# BusinessCard.net
KiCad netlist of a schematic drawn in EAGLE
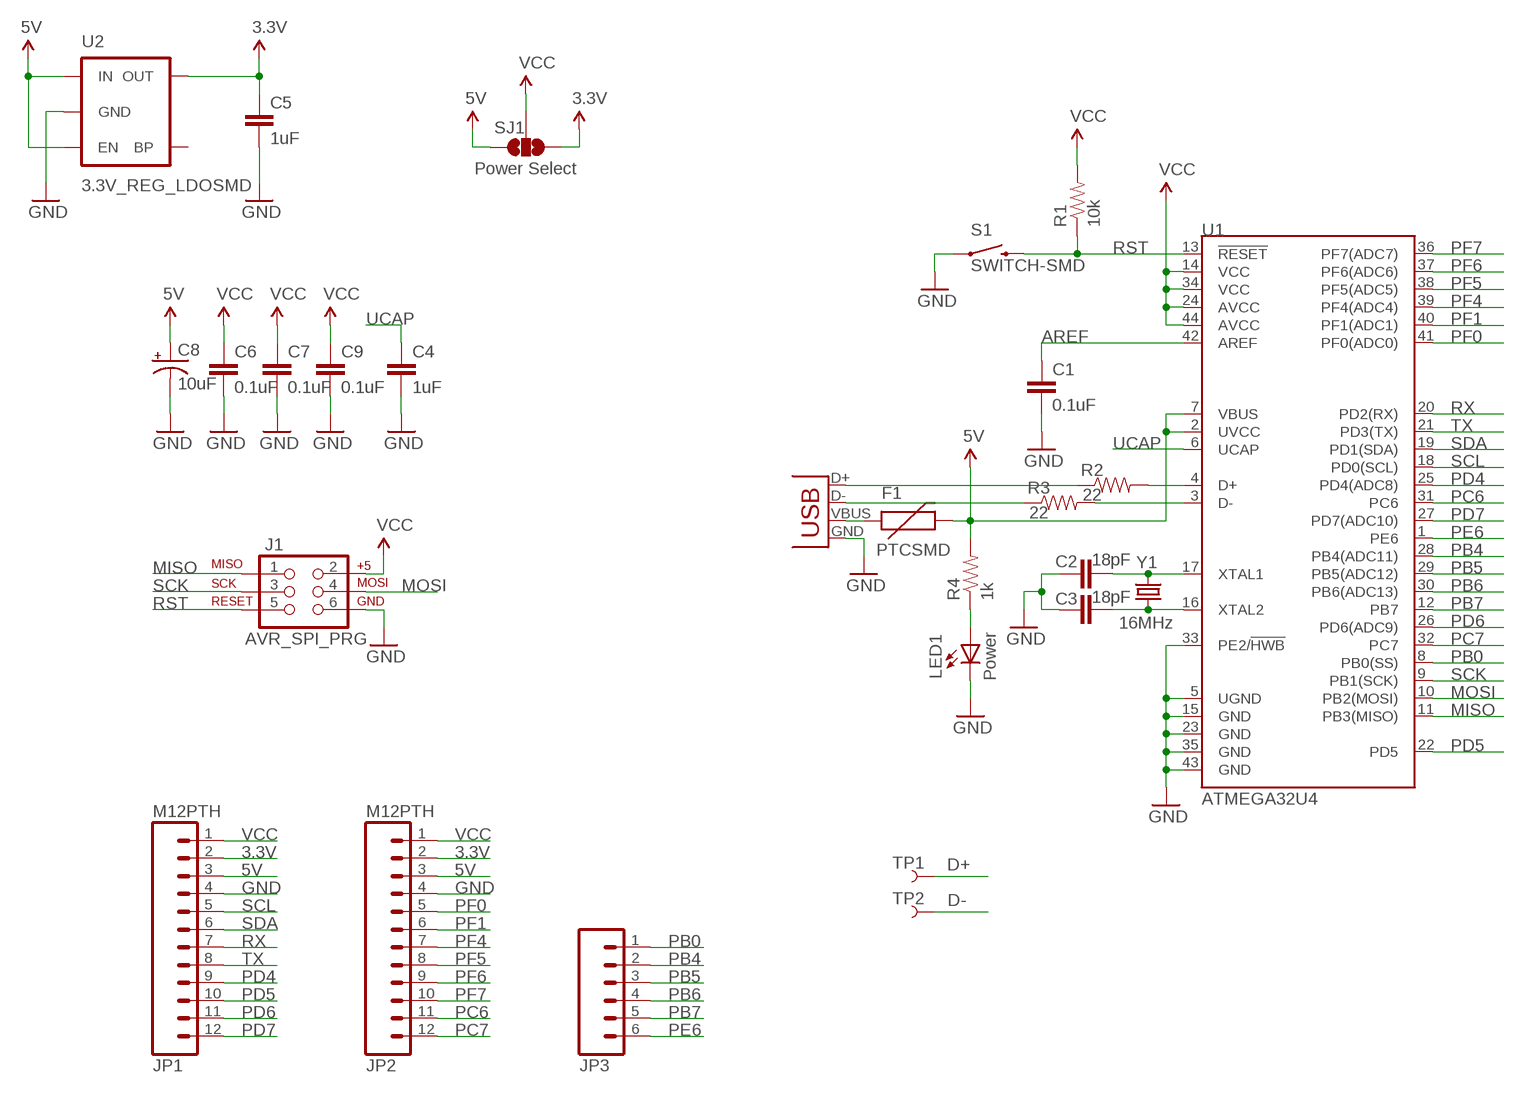
[diagram p0: schematic, sheet 1]

(export (version "E")
  (design (tool "Eeschema 10.0.6"))
  (components
    (comp (ref "C1")
      (value "0.1uF")
      (footprint "eagle-import:0402-CAP")
      (libsource (lib "eagle-import") (part "CAP0402-CAP"))
    )
    (comp (ref "C2")
      (value "18pF")
      (footprint "eagle-import:0402-CAP")
      (libsource (lib "eagle-import") (part "CAP0402-CAP"))
    )
    (comp (ref "C3")
      (value "18pF")
      (footprint "eagle-import:0402-CAP")
      (libsource (lib "eagle-import") (part "CAP0402-CAP"))
    )
    (comp (ref "C4")
      (value "1uF")
      (footprint "eagle-import:0402-CAP")
      (libsource (lib "eagle-import") (part "CAP0402-CAP"))
    )
    (comp (ref "C5")
      (value "1uF")
      (footprint "eagle-import:0402-CAP")
      (libsource (lib "eagle-import") (part "CAP0402-CAP"))
    )
    (comp (ref "C6")
      (value "0.1uF")
      (footprint "eagle-import:0402-CAP")
      (libsource (lib "eagle-import") (part "CAP0402-CAP"))
    )
    (comp (ref "C7")
      (value "0.1uF")
      (footprint "eagle-import:0402-CAP")
      (libsource (lib "eagle-import") (part "CAP0402-CAP"))
    )
    (comp (ref "C8")
      (value "10uF")
      (footprint "eagle-import:EIA3216")
      (libsource (lib "eagle-import") (part "CAP_POL1206"))
    )
    (comp (ref "C9")
      (value "0.1uF")
      (footprint "eagle-import:0402-CAP")
      (libsource (lib "eagle-import") (part "CAP0402-CAP"))
    )
    (comp (ref "F1")
      (value "PTCSMD")
      (footprint "eagle-import:PTC-1206")
      (libsource (lib "eagle-import") (part "PTCSMD"))
    )
    (comp (ref "J1")
      (value "AVR_SPI_PRG")
      (footprint "eagle-import:2X3")
      (libsource (lib "eagle-import") (part "AVR_SPI_PRG_6PTH"))
    )
    (comp (ref "JP1")
      (value "M12PTH")
      (footprint "eagle-import:1X12")
      (libsource (lib "eagle-import") (part "M12PTH"))
    )
    (comp (ref "JP2")
      (value "M12PTH")
      (footprint "eagle-import:1X12")
      (libsource (lib "eagle-import") (part "M12PTH"))
    )
    (comp (ref "JP3")
      (value "M06SIP")
      (footprint "eagle-import:1X06")
      (libsource (lib "eagle-import") (part "M06SIP"))
    )
    (comp (ref "LED1")
      (value "Power")
      (footprint "eagle-import:LED-0603")
      (libsource (lib "eagle-import") (part "LED0603"))
    )
    (comp (ref "R1")
      (value "10k")
      (footprint "eagle-import:0402-RES")
      (libsource (lib "eagle-import") (part "RESISTOR0402-RES"))
    )
    (comp (ref "R2")
      (value "22")
      (footprint "eagle-import:0402-RES")
      (libsource (lib "eagle-import") (part "RESISTOR0402-RES"))
    )
    (comp (ref "R3")
      (value "22")
      (footprint "eagle-import:0402-RES")
      (libsource (lib "eagle-import") (part "RESISTOR0402-RES"))
    )
    (comp (ref "R4")
      (value "1k")
      (footprint "eagle-import:0402-RES")
      (libsource (lib "eagle-import") (part "RESISTOR0402-RES"))
    )
    (comp (ref "S1")
      (value "SWITCH-SMD")
      (footprint "eagle-import:TACTILE_SWITCH_SMD")
      (libsource (lib "eagle-import") (part "SWITCH-MOMENTARY-2SMD"))
    )
    (comp (ref "SJ1")
      (value "Power Select")
      (footprint "eagle-import:SJ_3_PASTE2&3")
      (libsource (lib "eagle-import") (part "SOLDERJUMPER_2WAYPASTE2&3"))
    )
    (comp (ref "TP1")
      (value "TEST-POINT3")
      (footprint "eagle-import:PAD.03X.03")
      (libsource (lib "eagle-import") (part "TEST-POINT3"))
    )
    (comp (ref "TP2")
      (value "TEST-POINT3")
      (footprint "eagle-import:PAD.03X.03")
      (libsource (lib "eagle-import") (part "TEST-POINT3"))
    )
    (comp (ref "U1")
      (value "ATMEGA32U4")
      (footprint "eagle-import:QFN-44-NOPAD")
      (libsource (lib "eagle-import") (part "ATMEGA32U4QFN2"))
    )
    (comp (ref "U2")
      (value "3.3V_REG_LDOSMD")
      (footprint "eagle-import:SOT23-5")
      (libsource (lib "eagle-import") (part "V_REG_LDOSMD"))
    )
    (comp (ref "X1")
      (value "USBSMD")
      (footprint "eagle-import:USB-MINIB")
      (libsource (lib "eagle-import") (part "USBSMD"))
    )
    (comp (ref "Y1")
      (value "16MHz")
      (footprint "eagle-import:CRYSTAL-SMD-5X3")
      (libsource (lib "eagle-import") (part "CRYSTAL5X3"))
    )
  )
  (nets
    (net (code "1") (name "/AREF") (class "Default")
      (node (ref "C1") (pin "1") (pinfunction "1_1") (pintype "passive"))
      (node (ref "U1") (pin "42") (pinfunction "AREF_42") (pintype "bidirectional"))
    )
    (net (code "2") (name "/D+") (class "Default")
      (node (ref "R2") (pin "1") (pinfunction "1_1") (pintype "passive"))
      (node (ref "TP1") (pin "P$1") (pinfunction "1_P$1") (pintype "bidirectional"))
      (node (ref "X1") (pin "D+") (pinfunction "D+_D+") (pintype "bidirectional"))
    )
    (net (code "3") (name "/D-") (class "Default")
      (node (ref "R3") (pin "1") (pinfunction "1_1") (pintype "passive"))
      (node (ref "TP2") (pin "P$1") (pinfunction "1_P$1") (pintype "bidirectional"))
      (node (ref "X1") (pin "D-") (pinfunction "D-_D-") (pintype "bidirectional"))
    )
    (net (code "4") (name "/MISO") (class "Default")
      (node (ref "J1") (pin "1") (pinfunction "1_1") (pintype "passive"))
      (node (ref "U1") (pin "11") (pinfunction "PB3(MISO)_11") (pintype "bidirectional"))
    )
    (net (code "5") (name "/MOSI") (class "Default")
      (node (ref "J1") (pin "4") (pinfunction "4_4") (pintype "passive"))
      (node (ref "U1") (pin "10") (pinfunction "PB2(MOSI)_10") (pintype "bidirectional"))
    )
    (net (code "6") (name "/PB0") (class "Default")
      (node (ref "JP3") (pin "1") (pinfunction "1_1") (pintype "passive"))
      (node (ref "U1") (pin "8") (pinfunction "PB0(SS)_8") (pintype "bidirectional"))
    )
    (net (code "7") (name "/PB4") (class "Default")
      (node (ref "JP3") (pin "2") (pinfunction "2_2") (pintype "passive"))
      (node (ref "U1") (pin "28") (pinfunction "PB4(ADC11)_28") (pintype "bidirectional"))
    )
    (net (code "8") (name "/PB5") (class "Default")
      (node (ref "JP3") (pin "3") (pinfunction "3_3") (pintype "passive"))
      (node (ref "U1") (pin "29") (pinfunction "PB5(ADC12)_29") (pintype "bidirectional"))
    )
    (net (code "9") (name "/PB6") (class "Default")
      (node (ref "JP3") (pin "4") (pinfunction "4_4") (pintype "passive"))
      (node (ref "U1") (pin "30") (pinfunction "PB6(ADC13)_30") (pintype "bidirectional"))
    )
    (net (code "10") (name "/PB7") (class "Default")
      (node (ref "JP3") (pin "5") (pinfunction "5_5") (pintype "passive"))
      (node (ref "U1") (pin "12") (pinfunction "PB7_12") (pintype "bidirectional"))
    )
    (net (code "11") (name "/PC6") (class "Default")
      (node (ref "JP2") (pin "11") (pinfunction "11_11") (pintype "passive"))
      (node (ref "U1") (pin "31") (pinfunction "PC6_31") (pintype "bidirectional"))
    )
    (net (code "12") (name "/PC7") (class "Default")
      (node (ref "JP2") (pin "12") (pinfunction "12_12") (pintype "passive"))
      (node (ref "U1") (pin "32") (pinfunction "PC7_32") (pintype "bidirectional"))
    )
    (net (code "13") (name "/PD4") (class "Default")
      (node (ref "JP1") (pin "9") (pinfunction "9_9") (pintype "passive"))
      (node (ref "U1") (pin "25") (pinfunction "PD4(ADC8)_25") (pintype "bidirectional"))
    )
    (net (code "14") (name "/PD5") (class "Default")
      (node (ref "JP1") (pin "10") (pinfunction "10_10") (pintype "passive"))
      (node (ref "U1") (pin "22") (pinfunction "PD5_22") (pintype "bidirectional"))
    )
    (net (code "15") (name "/PD6") (class "Default")
      (node (ref "JP1") (pin "11") (pinfunction "11_11") (pintype "passive"))
      (node (ref "U1") (pin "26") (pinfunction "PD6(ADC9)_26") (pintype "bidirectional"))
    )
    (net (code "16") (name "/PD7") (class "Default")
      (node (ref "JP1") (pin "12") (pinfunction "12_12") (pintype "passive"))
      (node (ref "U1") (pin "27") (pinfunction "PD7(ADC10)_27") (pintype "bidirectional"))
    )
    (net (code "17") (name "/PE6") (class "Default")
      (node (ref "JP3") (pin "6") (pinfunction "6_6") (pintype "passive"))
      (node (ref "U1") (pin "1") (pinfunction "PE6_1") (pintype "bidirectional"))
    )
    (net (code "18") (name "/PF0") (class "Default")
      (node (ref "JP2") (pin "5") (pinfunction "5_5") (pintype "passive"))
      (node (ref "U1") (pin "41") (pinfunction "PF0(ADC0)_41") (pintype "bidirectional"))
    )
    (net (code "19") (name "/PF1") (class "Default")
      (node (ref "JP2") (pin "6") (pinfunction "6_6") (pintype "passive"))
      (node (ref "U1") (pin "40") (pinfunction "PF1(ADC1)_40") (pintype "bidirectional"))
    )
    (net (code "20") (name "/PF4") (class "Default")
      (node (ref "JP2") (pin "7") (pinfunction "7_7") (pintype "passive"))
      (node (ref "U1") (pin "39") (pinfunction "PF4(ADC4)_39") (pintype "bidirectional"))
    )
    (net (code "21") (name "/PF5") (class "Default")
      (node (ref "JP2") (pin "8") (pinfunction "8_8") (pintype "passive"))
      (node (ref "U1") (pin "38") (pinfunction "PF5(ADC5)_38") (pintype "bidirectional"))
    )
    (net (code "22") (name "/PF6") (class "Default")
      (node (ref "JP2") (pin "9") (pinfunction "9_9") (pintype "passive"))
      (node (ref "U1") (pin "37") (pinfunction "PF6(ADC6)_37") (pintype "bidirectional"))
    )
    (net (code "23") (name "/PF7") (class "Default")
      (node (ref "JP2") (pin "10") (pinfunction "10_10") (pintype "passive"))
      (node (ref "U1") (pin "36") (pinfunction "PF7(ADC7)_36") (pintype "bidirectional"))
    )
    (net (code "24") (name "/RST") (class "Default")
      (node (ref "J1") (pin "5") (pinfunction "5_5") (pintype "passive"))
      (node (ref "R1") (pin "1") (pinfunction "1_1") (pintype "passive"))
      (node (ref "S1") (pin "3") (pinfunction "2_3") (pintype "passive"))
      (node (ref "U1") (pin "13") (pinfunction "~{RESET}_13") (pintype "bidirectional"))
    )
    (net (code "25") (name "/RX") (class "Default")
      (node (ref "JP1") (pin "7") (pinfunction "7_7") (pintype "passive"))
      (node (ref "U1") (pin "20") (pinfunction "PD2(RX)_20") (pintype "bidirectional"))
    )
    (net (code "26") (name "/SCK") (class "Default")
      (node (ref "J1") (pin "3") (pinfunction "3_3") (pintype "passive"))
      (node (ref "U1") (pin "9") (pinfunction "PB1(SCK)_9") (pintype "bidirectional"))
    )
    (net (code "27") (name "/SCL") (class "Default")
      (node (ref "JP1") (pin "5") (pinfunction "5_5") (pintype "passive"))
      (node (ref "U1") (pin "18") (pinfunction "PD0(SCL)_18") (pintype "bidirectional"))
    )
    (net (code "28") (name "/SDA") (class "Default")
      (node (ref "JP1") (pin "6") (pinfunction "6_6") (pintype "passive"))
      (node (ref "U1") (pin "19") (pinfunction "PD1(SDA)_19") (pintype "bidirectional"))
    )
    (net (code "29") (name "/TX") (class "Default")
      (node (ref "JP1") (pin "8") (pinfunction "8_8") (pintype "passive"))
      (node (ref "U1") (pin "21") (pinfunction "PD3(TX)_21") (pintype "bidirectional"))
    )
    (net (code "30") (name "/UCAP") (class "Default")
      (node (ref "C4") (pin "1") (pinfunction "1_1") (pintype "passive"))
      (node (ref "U1") (pin "6") (pinfunction "UCAP_6") (pintype "bidirectional"))
    )
    (net (code "31") (name "3.3V") (class "Default")
      (node (ref "C5") (pin "1") (pinfunction "1_1") (pintype "passive"))
      (node (ref "JP1") (pin "2") (pinfunction "2_2") (pintype "passive"))
      (node (ref "JP2") (pin "2") (pinfunction "2_2") (pintype "passive"))
      (node (ref "SJ1") (pin "1") (pinfunction "1_1") (pintype "passive"))
      (node (ref "U2") (pin "5") (pinfunction "OUT_5") (pintype "passive"))
    )
    (net (code "32") (name "5V") (class "Default")
      (node (ref "C8") (pin "A") (pinfunction "+_A") (pintype "passive"))
      (node (ref "F1") (pin "2") (pinfunction "2_2") (pintype "bidirectional"))
      (node (ref "JP1") (pin "3") (pinfunction "3_3") (pintype "passive"))
      (node (ref "JP2") (pin "3") (pinfunction "3_3") (pintype "passive"))
      (node (ref "R4") (pin "2") (pinfunction "2_2") (pintype "passive"))
      (node (ref "SJ1") (pin "3") (pinfunction "3_3") (pintype "passive"))
      (node (ref "U1") (pin "2") (pinfunction "UVCC_2") (pintype "bidirectional"))
      (node (ref "U1") (pin "7") (pinfunction "VBUS_7") (pintype "bidirectional"))
      (node (ref "U2") (pin "1") (pinfunction "IN_1") (pintype "input"))
      (node (ref "U2") (pin "3") (pinfunction "EN_3") (pintype "input"))
    )
    (net (code "33") (name "GND") (class "Default")
      (node (ref "C1") (pin "2") (pinfunction "2_2") (pintype "passive"))
      (node (ref "C2") (pin "1") (pinfunction "1_1") (pintype "passive"))
      (node (ref "C3") (pin "1") (pinfunction "1_1") (pintype "passive"))
      (node (ref "C4") (pin "2") (pinfunction "2_2") (pintype "passive"))
      (node (ref "C5") (pin "2") (pinfunction "2_2") (pintype "passive"))
      (node (ref "C6") (pin "2") (pinfunction "2_2") (pintype "passive"))
      (node (ref "C7") (pin "2") (pinfunction "2_2") (pintype "passive"))
      (node (ref "C8") (pin "C") (pinfunction "-_C") (pintype "passive"))
      (node (ref "C9") (pin "2") (pinfunction "2_2") (pintype "passive"))
      (node (ref "J1") (pin "6") (pinfunction "6_6") (pintype "passive"))
      (node (ref "JP1") (pin "4") (pinfunction "4_4") (pintype "passive"))
      (node (ref "JP2") (pin "4") (pinfunction "4_4") (pintype "passive"))
      (node (ref "LED1") (pin "C") (pinfunction "C_C") (pintype "passive"))
      (node (ref "S1") (pin "1") (pinfunction "1_1") (pintype "passive"))
      (node (ref "U1") (pin "15") (pinfunction "GND_15") (pintype "bidirectional"))
      (node (ref "U1") (pin "23") (pinfunction "GND_23") (pintype "bidirectional"))
      (node (ref "U1") (pin "33") (pinfunction "PE2/~{HWB}_33") (pintype "bidirectional"))
      (node (ref "U1") (pin "35") (pinfunction "GND_35") (pintype "bidirectional"))
      (node (ref "U1") (pin "43") (pinfunction "GND_43") (pintype "bidirectional"))
      (node (ref "U1") (pin "5") (pinfunction "UGND_5") (pintype "bidirectional"))
      (node (ref "U2") (pin "2") (pinfunction "GND_2") (pintype "input"))
      (node (ref "X1") (pin "GND") (pinfunction "GND_GND") (pintype "bidirectional"))
    )
    (net (code "34") (name "Net-(F1-Pad1)") (class "Default")
      (node (ref "F1") (pin "1") (pinfunction "1_1") (pintype "bidirectional"))
      (node (ref "X1") (pin "VBUS") (pinfunction "VBUS_VBUS") (pintype "bidirectional"))
    )
    (net (code "35") (name "Net-(LED1-PadA)") (class "Default")
      (node (ref "LED1") (pin "A") (pinfunction "A_A") (pintype "passive"))
      (node (ref "R4") (pin "1") (pinfunction "1_1") (pintype "passive"))
    )
    (net (code "36") (name "Net-(U1-D+)") (class "Default")
      (node (ref "R2") (pin "2") (pinfunction "2_2") (pintype "passive"))
      (node (ref "U1") (pin "4") (pinfunction "D+_4") (pintype "bidirectional"))
    )
    (net (code "37") (name "Net-(U1-D-)") (class "Default")
      (node (ref "R3") (pin "2") (pinfunction "2_2") (pintype "passive"))
      (node (ref "U1") (pin "3") (pinfunction "D-_3") (pintype "bidirectional"))
    )
    (net (code "38") (name "Net-(U1-XTAL1)") (class "Default")
      (node (ref "C2") (pin "2") (pinfunction "2_2") (pintype "passive"))
      (node (ref "U1") (pin "17") (pinfunction "XTAL1_17") (pintype "bidirectional"))
      (node (ref "Y1") (pin "3") (pinfunction "2_3") (pintype "passive"))
    )
    (net (code "39") (name "Net-(U1-XTAL2)") (class "Default")
      (node (ref "C3") (pin "2") (pinfunction "2_2") (pintype "passive"))
      (node (ref "U1") (pin "16") (pinfunction "XTAL2_16") (pintype "bidirectional"))
      (node (ref "Y1") (pin "1") (pinfunction "1_1") (pintype "passive"))
    )
    (net (code "40") (name "VCC") (class "Default")
      (node (ref "C6") (pin "1") (pinfunction "1_1") (pintype "passive"))
      (node (ref "C7") (pin "1") (pinfunction "1_1") (pintype "passive"))
      (node (ref "C9") (pin "1") (pinfunction "1_1") (pintype "passive"))
      (node (ref "J1") (pin "2") (pinfunction "2_2") (pintype "passive"))
      (node (ref "JP1") (pin "1") (pinfunction "1_1") (pintype "passive"))
      (node (ref "JP2") (pin "1") (pinfunction "1_1") (pintype "passive"))
      (node (ref "R1") (pin "2") (pinfunction "2_2") (pintype "passive"))
      (node (ref "SJ1") (pin "2") (pinfunction "2_2") (pintype "passive"))
      (node (ref "U1") (pin "14") (pinfunction "VCC_14") (pintype "bidirectional"))
      (node (ref "U1") (pin "24") (pinfunction "AVCC_24") (pintype "bidirectional"))
      (node (ref "U1") (pin "34") (pinfunction "VCC_34") (pintype "bidirectional"))
      (node (ref "U1") (pin "44") (pinfunction "AVCC_44") (pintype "bidirectional"))
    )
    (net (code "41") (name "unconnected-(U2-BP-Pad4)") (class "Default")
      (node (ref "U2") (pin "4") (pinfunction "BP_4") (pintype "input"))
    )
  )
)
